# STMkaN.net
KiCad netlist of a schematic drawn in Altium Designer
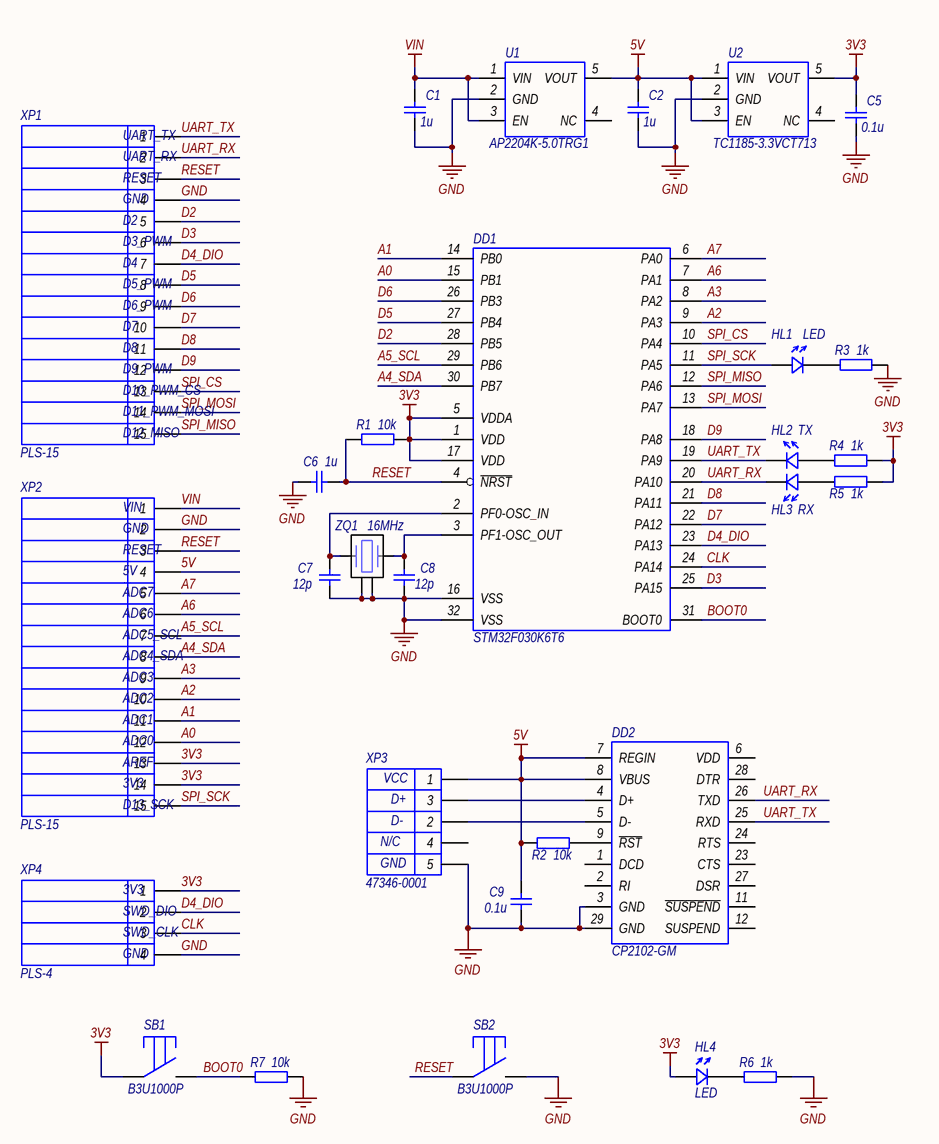
[diagram p0: STMkaN.SchDoc]

(export (version "E")
  (design (tool "Eeschema 10.0.6"))
  (components
    (comp (ref "C1")
      (value "1u")
      (footprint "0603C")
      (description "Capacitor")
      (libsource (lib "KDI") (part "SMD-CAP"))
    )
    (comp (ref "C2")
      (value "1u")
      (footprint "0603C")
      (description "Capacitor")
      (libsource (lib "KDI") (part "SMD-CAP"))
    )
    (comp (ref "C5")
      (value "0.1u")
      (footprint "0603C")
      (description "Capacitor")
      (libsource (lib "KDI") (part "SMD-CAP"))
    )
    (comp (ref "C6")
      (value "1u")
      (footprint "0603C")
      (description "Capacitor")
      (libsource (lib "KDI") (part "SMD-CAP"))
    )
    (comp (ref "C7")
      (value "12p")
      (footprint "0603C")
      (description "Capacitor")
      (libsource (lib "KDI") (part "SMD-CAP"))
    )
    (comp (ref "C8")
      (value "12p")
      (footprint "0603C")
      (description "Capacitor")
      (libsource (lib "KDI") (part "SMD-CAP"))
    )
    (comp (ref "C9")
      (value "0.1u")
      (footprint "0603C")
      (description "Capacitor")
      (libsource (lib "KDI") (part "SMD-CAP"))
    )
    (comp (ref "DD1")
      (value "STM32F030K6T6")
      (footprint "TQFP-32")
      (description "Controller")
      (libsource (lib "KDI") (part "STM32F030K6T6"))
    )
    (comp (ref "DD2") (value "CP2102-GM") (footprint "QFN-28") (libsource (lib "KDI") (part "CP2102")))
    (comp (ref "HL1") (value "LED") (footprint "0603L") (libsource (lib "KDI") (part "LEDx1")))
    (comp (ref "HL2")
      (value "TX")
      (footprint "0603L")
      (description "LED")
      (libsource (lib "KDI") (part "LEDx1"))
    )
    (comp (ref "HL3")
      (value "RX")
      (footprint "0603L")
      (description "LED")
      (libsource (lib "KDI") (part "LEDx1"))
    )
    (comp (ref "HL4") (value "LED") (footprint "0603L") (libsource (lib "KDI") (part "LEDx1")))
    (comp (ref "R1")
      (value "10k")
      (footprint "0603R")
      (description "Resistor")
      (libsource (lib "KDI") (part "SMD-RES"))
    )
    (comp (ref "R2")
      (value "10k")
      (footprint "0603R")
      (description "Resistor")
      (libsource (lib "KDI") (part "SMD-RES"))
    )
    (comp (ref "R3")
      (value "1k")
      (footprint "0603R")
      (description "Resistor")
      (libsource (lib "KDI") (part "SMD-RES"))
    )
    (comp (ref "R4")
      (value "1k")
      (footprint "0603R")
      (description "Resistor")
      (libsource (lib "KDI") (part "SMD-RES"))
    )
    (comp (ref "R5")
      (value "1k")
      (footprint "0603R")
      (description "Resistor")
      (libsource (lib "KDI") (part "SMD-RES"))
    )
    (comp (ref "R6")
      (value "1k")
      (footprint "0603R")
      (description "Resistor")
      (libsource (lib "KDI") (part "SMD-RES"))
    )
    (comp (ref "R7")
      (value "10k")
      (footprint "0603R")
      (description "Resistor")
      (libsource (lib "KDI") (part "SMD-RES"))
    )
    (comp (ref "SB1")
      (value "B3U1000P")
      (footprint "B3U1000P")
      (description "Button")
      (libsource (lib "KDI") (part "SWITCH"))
    )
    (comp (ref "SB2")
      (value "B3U1000P")
      (footprint "B3U1000P")
      (description "Button")
      (libsource (lib "KDI") (part "SWITCH"))
    )
    (comp (ref "U1")
      (value "AP2204K-5.0TRG1")
      (footprint "SOT23-5")
      (description "POWER")
      (libsource (lib "KDI") (part "TPS76333DBVR"))
    )
    (comp (ref "U2")
      (value "TC1185-3.3VCT713")
      (footprint "SOT23-5")
      (description "POWER")
      (libsource (lib "KDI") (part "TPS76333DBVR"))
    )
    (comp (ref "XP1")
      (value "PLS-15")
      (footprint "PLS-15")
      (description "Connector")
      (libsource (lib "KDI") (part "XP15"))
    )
    (comp (ref "XP2")
      (value "PLS-15")
      (footprint "PLS-15")
      (description "Connector")
      (libsource (lib "KDI") (part "XP15"))
    )
    (comp (ref "XP3")
      (value "47346-0001")
      (footprint "USB-micro")
      (description "Connector")
      (libsource (lib "KDI") (part "USB-micro"))
    )
    (comp (ref "XP4")
      (value "PLS-4")
      (footprint "PLS-4")
      (description "Connector")
      (libsource (lib "KDI") (part "XP4"))
    )
    (comp (ref "ZQ1")
      (value "16MHz")
      (footprint "SMD0302C4")
      (description "Quartz")
      (libsource (lib "KDI") (part "Quartz"))
    )
  )
  (nets
    (net (code "1") (name "/A0") (class "Default")
      (node (ref "DD1") (pin "15") (pinfunction "PB1_15") (pintype "passive"))
      (node (ref "XP2") (pin "12") (pinfunction "12_12") (pintype "passive"))
    )
    (net (code "2") (name "/A1") (class "Default")
      (node (ref "DD1") (pin "14") (pinfunction "PB0_14") (pintype "passive"))
      (node (ref "XP2") (pin "11") (pinfunction "11_11") (pintype "passive"))
    )
    (net (code "3") (name "/A2") (class "Default")
      (node (ref "DD1") (pin "9") (pinfunction "PA3_9") (pintype "passive"))
      (node (ref "XP2") (pin "10") (pinfunction "10_10") (pintype "passive"))
    )
    (net (code "4") (name "/A3") (class "Default")
      (node (ref "DD1") (pin "8") (pinfunction "PA2_8") (pintype "passive"))
      (node (ref "XP2") (pin "9") (pinfunction "9_9") (pintype "passive"))
    )
    (net (code "5") (name "/A4_SDA") (class "Default")
      (node (ref "DD1") (pin "30") (pinfunction "PB7_30") (pintype "passive"))
      (node (ref "XP2") (pin "8") (pinfunction "8_8") (pintype "passive"))
    )
    (net (code "6") (name "/A5_SCL") (class "Default")
      (node (ref "DD1") (pin "29") (pinfunction "PB6_29") (pintype "passive"))
      (node (ref "XP2") (pin "7") (pinfunction "7_7") (pintype "passive"))
    )
    (net (code "7") (name "/A6") (class "Default")
      (node (ref "DD1") (pin "7") (pinfunction "PA1_7") (pintype "passive"))
      (node (ref "XP2") (pin "6") (pinfunction "6_6") (pintype "passive"))
    )
    (net (code "8") (name "/A7") (class "Default")
      (node (ref "DD1") (pin "6") (pinfunction "PA0_6") (pintype "passive"))
      (node (ref "XP2") (pin "5") (pinfunction "5_5") (pintype "passive"))
    )
    (net (code "9") (name "/BOOT0") (class "Default")
      (node (ref "DD1") (pin "31") (pinfunction "BOOT0_31") (pintype "passive"))
      (node (ref "R7") (pin "1") (pinfunction "1_1") (pintype "passive"))
      (node (ref "SB1") (pin "2") (pintype "passive"))
    )
    (net (code "10") (name "/CLK") (class "Default")
      (node (ref "DD1") (pin "24") (pinfunction "PA14_24") (pintype "passive"))
      (node (ref "XP4") (pin "3") (pinfunction "3_3") (pintype "passive"))
    )
    (net (code "11") (name "/D2") (class "Default")
      (node (ref "DD1") (pin "28") (pinfunction "PB5_28") (pintype "passive"))
      (node (ref "XP1") (pin "5") (pinfunction "5_5") (pintype "passive"))
    )
    (net (code "12") (name "/D3") (class "Default")
      (node (ref "DD1") (pin "25") (pinfunction "PA15_25") (pintype "passive"))
      (node (ref "XP1") (pin "6") (pinfunction "6_6") (pintype "passive"))
    )
    (net (code "13") (name "/D4_DIO") (class "Default")
      (node (ref "DD1") (pin "23") (pinfunction "PA13_23") (pintype "passive"))
      (node (ref "XP1") (pin "7") (pinfunction "7_7") (pintype "passive"))
      (node (ref "XP4") (pin "2") (pinfunction "2_2") (pintype "passive"))
    )
    (net (code "14") (name "/D5") (class "Default")
      (node (ref "DD1") (pin "27") (pinfunction "PB4_27") (pintype "passive"))
      (node (ref "XP1") (pin "8") (pinfunction "8_8") (pintype "passive"))
    )
    (net (code "15") (name "/D6") (class "Default")
      (node (ref "DD1") (pin "26") (pinfunction "PB3_26") (pintype "passive"))
      (node (ref "XP1") (pin "9") (pinfunction "9_9") (pintype "passive"))
    )
    (net (code "16") (name "/D7") (class "Default")
      (node (ref "DD1") (pin "22") (pinfunction "PA12_22") (pintype "passive"))
      (node (ref "XP1") (pin "10") (pinfunction "10_10") (pintype "passive"))
    )
    (net (code "17") (name "/D8") (class "Default")
      (node (ref "DD1") (pin "21") (pinfunction "PA11_21") (pintype "passive"))
      (node (ref "XP1") (pin "11") (pinfunction "11_11") (pintype "passive"))
    )
    (net (code "18") (name "/D9") (class "Default")
      (node (ref "DD1") (pin "18") (pinfunction "PA8_18") (pintype "passive"))
      (node (ref "XP1") (pin "12") (pinfunction "12_12") (pintype "passive"))
    )
    (net (code "19") (name "/RESET") (class "Default")
      (node (ref "C6") (pin "1") (pinfunction "1_1") (pintype "passive"))
      (node (ref "DD1") (pin "4") (pinfunction "~{NRST}_4") (pintype "passive"))
      (node (ref "R1") (pin "2") (pinfunction "2_2") (pintype "passive"))
      (node (ref "SB2") (pin "1") (pintype "passive"))
      (node (ref "XP1") (pin "3") (pinfunction "3_3") (pintype "passive"))
      (node (ref "XP2") (pin "3") (pinfunction "3_3") (pintype "passive"))
    )
    (net (code "20") (name "/SPI_CS") (class "Default")
      (node (ref "DD1") (pin "10") (pinfunction "PA4_10") (pintype "passive"))
      (node (ref "XP1") (pin "13") (pinfunction "13_13") (pintype "passive"))
    )
    (net (code "21") (name "/SPI_MISO") (class "Default")
      (node (ref "DD1") (pin "12") (pinfunction "PA6_12") (pintype "passive"))
      (node (ref "XP1") (pin "15") (pinfunction "15_15") (pintype "passive"))
    )
    (net (code "22") (name "/SPI_MOSI") (class "Default")
      (node (ref "DD1") (pin "13") (pinfunction "PA7_13") (pintype "passive"))
      (node (ref "XP1") (pin "14") (pinfunction "14_14") (pintype "passive"))
    )
    (net (code "23") (name "/SPI_SCK") (class "Default")
      (node (ref "DD1") (pin "11") (pinfunction "PA5_11") (pintype "passive"))
      (node (ref "HL1") (pin "2") (pinfunction "A_2") (pintype "passive"))
      (node (ref "XP2") (pin "15") (pinfunction "15_15") (pintype "passive"))
    )
    (net (code "24") (name "/UART_RX") (class "Default")
      (node (ref "DD1") (pin "20") (pinfunction "PA10_20") (pintype "passive"))
      (node (ref "DD2") (pin "26") (pinfunction "TXD_26") (pintype "passive"))
      (node (ref "HL3") (pin "1") (pinfunction "K_1") (pintype "passive"))
      (node (ref "XP1") (pin "2") (pinfunction "2_2") (pintype "passive"))
    )
    (net (code "25") (name "/UART_TX") (class "Default")
      (node (ref "DD1") (pin "19") (pinfunction "PA9_19") (pintype "passive"))
      (node (ref "DD2") (pin "25") (pinfunction "RXD_25") (pintype "passive"))
      (node (ref "HL2") (pin "1") (pinfunction "K_1") (pintype "passive"))
      (node (ref "XP1") (pin "1") (pinfunction "1_1") (pintype "passive"))
    )
    (net (code "26") (name "3V3") (class "Default")
      (node (ref "C5") (pin "2") (pinfunction "2_2") (pintype "passive"))
      (node (ref "DD1") (pin "1") (pinfunction "VDD_1") (pintype "passive"))
      (node (ref "DD1") (pin "17") (pinfunction "VDD_17") (pintype "passive"))
      (node (ref "DD1") (pin "5") (pinfunction "VDDA_5") (pintype "passive"))
      (node (ref "HL4") (pin "2") (pinfunction "A_2") (pintype "passive"))
      (node (ref "R1") (pin "1") (pinfunction "1_1") (pintype "passive"))
      (node (ref "R4") (pin "1") (pinfunction "1_1") (pintype "passive"))
      (node (ref "R5") (pin "1") (pinfunction "1_1") (pintype "passive"))
      (node (ref "SB1") (pin "1") (pintype "passive"))
      (node (ref "U2") (pin "5") (pinfunction "VOUT_5") (pintype "passive"))
      (node (ref "XP2") (pin "13") (pinfunction "13_13") (pintype "passive"))
      (node (ref "XP2") (pin "14") (pinfunction "14_14") (pintype "passive"))
      (node (ref "XP4") (pin "1") (pinfunction "1_1") (pintype "passive"))
    )
    (net (code "27") (name "5V") (class "Default")
      (node (ref "C2") (pin "2") (pinfunction "2_2") (pintype "passive"))
      (node (ref "C9") (pin "2") (pinfunction "2_2") (pintype "passive"))
      (node (ref "DD2") (pin "7") (pinfunction "REGIN_7") (pintype "passive"))
      (node (ref "DD2") (pin "8") (pinfunction "VBUS_8") (pintype "passive"))
      (node (ref "R2") (pin "1") (pinfunction "1_1") (pintype "passive"))
      (node (ref "U1") (pin "5") (pinfunction "VOUT_5") (pintype "passive"))
      (node (ref "U2") (pin "1") (pinfunction "VIN_1") (pintype "passive"))
      (node (ref "U2") (pin "3") (pinfunction "EN_3") (pintype "passive"))
      (node (ref "XP2") (pin "4") (pinfunction "4_4") (pintype "passive"))
      (node (ref "XP3") (pin "1") (pinfunction "1_1") (pintype "passive"))
    )
    (net (code "28") (name "GND") (class "Default")
      (node (ref "C1") (pin "1") (pinfunction "1_1") (pintype "passive"))
      (node (ref "C2") (pin "1") (pinfunction "1_1") (pintype "passive"))
      (node (ref "C5") (pin "1") (pinfunction "1_1") (pintype "passive"))
      (node (ref "C6") (pin "2") (pinfunction "2_2") (pintype "passive"))
      (node (ref "C7") (pin "1") (pinfunction "1_1") (pintype "passive"))
      (node (ref "C8") (pin "1") (pinfunction "1_1") (pintype "passive"))
      (node (ref "C9") (pin "1") (pinfunction "1_1") (pintype "passive"))
      (node (ref "DD1") (pin "16") (pinfunction "VSS_16") (pintype "passive"))
      (node (ref "DD1") (pin "32") (pinfunction "VSS_32") (pintype "passive"))
      (node (ref "DD2") (pin "29") (pinfunction "GND_29") (pintype "passive"))
      (node (ref "DD2") (pin "3") (pinfunction "GND_3") (pintype "passive"))
      (node (ref "R3") (pin "1") (pinfunction "1_1") (pintype "passive"))
      (node (ref "R6") (pin "1") (pinfunction "1_1") (pintype "passive"))
      (node (ref "R7") (pin "2") (pinfunction "2_2") (pintype "passive"))
      (node (ref "SB2") (pin "2") (pintype "passive"))
      (node (ref "U1") (pin "2") (pinfunction "GND_2") (pintype "passive"))
      (node (ref "U2") (pin "2") (pinfunction "GND_2") (pintype "passive"))
      (node (ref "XP1") (pin "4") (pinfunction "4_4") (pintype "passive"))
      (node (ref "XP2") (pin "2") (pinfunction "2_2") (pintype "passive"))
      (node (ref "XP3") (pin "5") (pinfunction "5_5") (pintype "passive"))
      (node (ref "XP4") (pin "4") (pinfunction "4_4") (pintype "passive"))
      (node (ref "ZQ1") (pin "2") (pinfunction "5_2") (pintype "passive"))
      (node (ref "ZQ1") (pin "4") (pinfunction "4_4") (pintype "passive"))
    )
    (net (code "29") (name "Net-(DD1-PF0-OSC_IN)") (class "Default")
      (node (ref "C7") (pin "2") (pinfunction "2_2") (pintype "passive"))
      (node (ref "DD1") (pin "2") (pinfunction "PF0-OSC_IN_2") (pintype "passive"))
      (node (ref "ZQ1") (pin "3") (pinfunction "3_3") (pintype "passive"))
    )
    (net (code "30") (name "Net-(DD1-PF1-OSC_OUT)") (class "Default")
      (node (ref "C8") (pin "2") (pinfunction "2_2") (pintype "passive"))
      (node (ref "DD1") (pin "3") (pinfunction "PF1-OSC_OUT_3") (pintype "passive"))
      (node (ref "ZQ1") (pin "1") (pinfunction "1_1") (pintype "passive"))
    )
    (net (code "31") (name "Net-(DD2-D+)") (class "Default")
      (node (ref "DD2") (pin "4") (pinfunction "D+_4") (pintype "passive"))
      (node (ref "XP3") (pin "3") (pinfunction "3_3") (pintype "passive"))
    )
    (net (code "32") (name "Net-(DD2-D-)") (class "Default")
      (node (ref "DD2") (pin "5") (pinfunction "D-_5") (pintype "passive"))
      (node (ref "XP3") (pin "2") (pinfunction "2_2") (pintype "passive"))
    )
    (net (code "33") (name "Net-(DD2-~{RST})") (class "Default")
      (node (ref "DD2") (pin "9") (pinfunction "~{RST}_9") (pintype "passive"))
      (node (ref "R2") (pin "2") (pinfunction "2_2") (pintype "passive"))
    )
    (net (code "34") (name "Net-(HL1-K)") (class "Default")
      (node (ref "HL1") (pin "1") (pinfunction "K_1") (pintype "passive"))
      (node (ref "R3") (pin "2") (pinfunction "2_2") (pintype "passive"))
    )
    (net (code "35") (name "Net-(HL2-A)") (class "Default")
      (node (ref "HL2") (pin "2") (pinfunction "A_2") (pintype "passive"))
      (node (ref "R4") (pin "2") (pinfunction "2_2") (pintype "passive"))
    )
    (net (code "36") (name "Net-(HL3-A)") (class "Default")
      (node (ref "HL3") (pin "2") (pinfunction "A_2") (pintype "passive"))
      (node (ref "R5") (pin "2") (pinfunction "2_2") (pintype "passive"))
    )
    (net (code "37") (name "Net-(HL4-K)") (class "Default")
      (node (ref "HL4") (pin "1") (pinfunction "K_1") (pintype "passive"))
      (node (ref "R6") (pin "2") (pinfunction "2_2") (pintype "passive"))
    )
    (net (code "38") (name "VIN") (class "Default")
      (node (ref "C1") (pin "2") (pinfunction "2_2") (pintype "passive"))
      (node (ref "U1") (pin "1") (pinfunction "VIN_1") (pintype "passive"))
      (node (ref "U1") (pin "3") (pinfunction "EN_3") (pintype "passive"))
      (node (ref "XP2") (pin "1") (pinfunction "1_1") (pintype "passive"))
    )
    (net (code "39") (name "unconnected-(DD2-CTS-Pad23)") (class "Default")
      (node (ref "DD2") (pin "23") (pinfunction "CTS_23") (pintype "passive"))
    )
    (net (code "40") (name "unconnected-(DD2-DCD-Pad1)") (class "Default")
      (node (ref "DD2") (pin "1") (pinfunction "DCD_1") (pintype "passive"))
    )
    (net (code "41") (name "unconnected-(DD2-DSR-Pad27)") (class "Default")
      (node (ref "DD2") (pin "27") (pinfunction "DSR_27") (pintype "passive"))
    )
    (net (code "42") (name "unconnected-(DD2-DTR-Pad28)") (class "Default")
      (node (ref "DD2") (pin "28") (pinfunction "DTR_28") (pintype "passive"))
    )
    (net (code "43") (name "unconnected-(DD2-RI-Pad2)") (class "Default")
      (node (ref "DD2") (pin "2") (pinfunction "RI_2") (pintype "passive"))
    )
    (net (code "44") (name "unconnected-(DD2-RTS-Pad24)") (class "Default")
      (node (ref "DD2") (pin "24") (pinfunction "RTS_24") (pintype "passive"))
    )
    (net (code "45") (name "unconnected-(DD2-SUSPEND-Pad12)") (class "Default")
      (node (ref "DD2") (pin "12") (pinfunction "SUSPEND_12") (pintype "passive"))
    )
    (net (code "46") (name "unconnected-(DD2-VDD-Pad6)") (class "Default")
      (node (ref "DD2") (pin "6") (pinfunction "VDD_6") (pintype "passive"))
    )
    (net (code "47") (name "unconnected-(DD2-~{SUSPEND}-Pad11)") (class "Default")
      (node (ref "DD2") (pin "11") (pinfunction "~{SUSPEND}_11") (pintype "passive"))
    )
    (net (code "48") (name "unconnected-(U1-NC-Pad4)") (class "Default")
      (node (ref "U1") (pin "4") (pinfunction "NC_4") (pintype "passive"))
    )
    (net (code "49") (name "unconnected-(U2-NC-Pad4)") (class "Default")
      (node (ref "U2") (pin "4") (pinfunction "NC_4") (pintype "passive"))
    )
    (net (code "50") (name "unconnected-(XP3-Pad4)") (class "Default")
      (node (ref "XP3") (pin "4") (pinfunction "4_4") (pintype "passive"))
    )
  )
)
